# Arduino_project_board.net
KiCad netlist of a schematic drawn in EAGLE
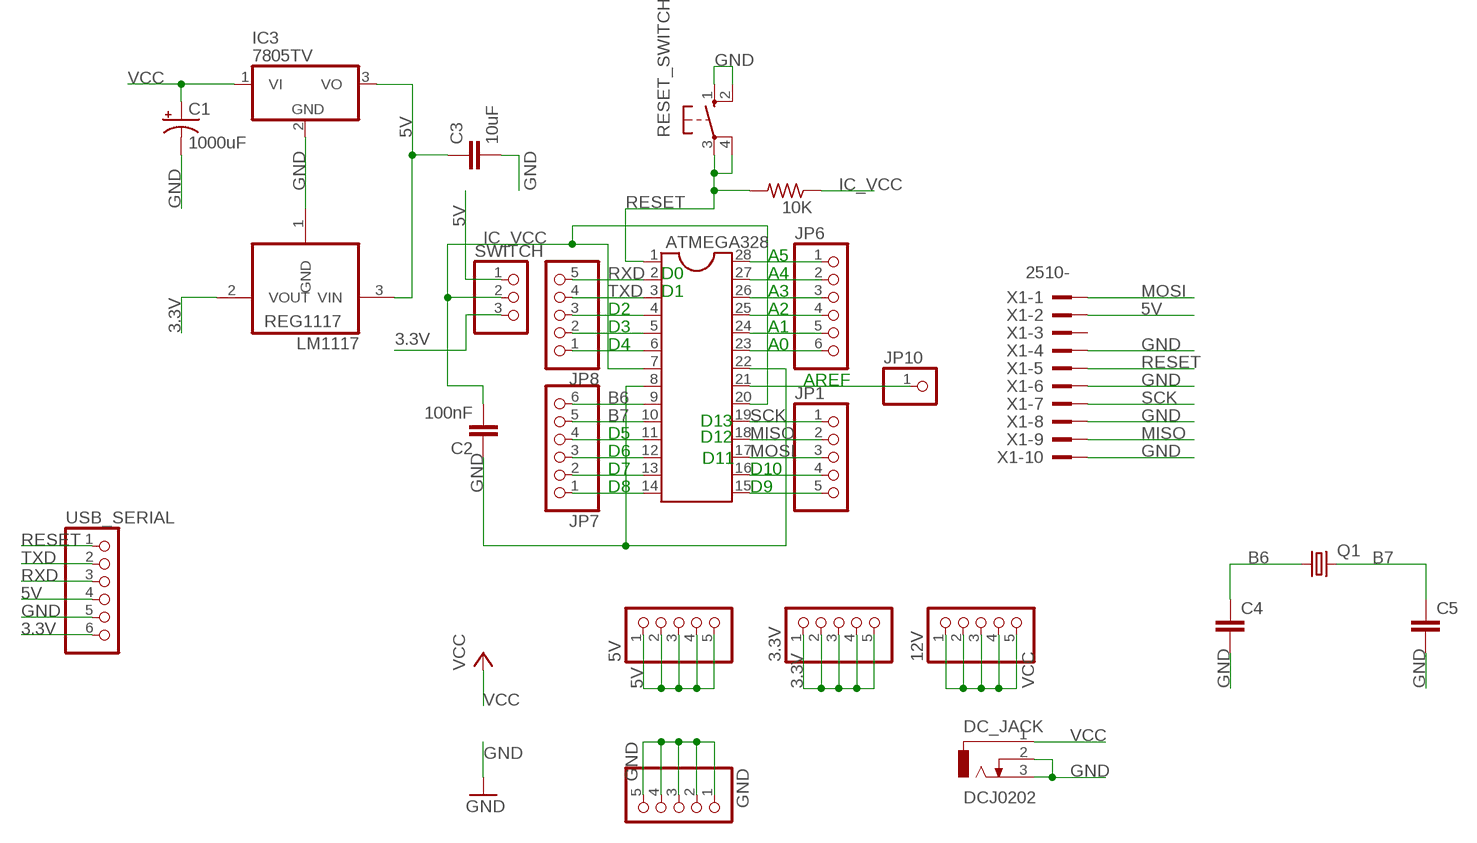
[diagram p0: schematic, sheet 1]

(export (version "E")
  (design (tool "Eeschema 10.0.6"))
  (components
    (comp (ref "3.3V")
      (value "PINHD-1X5")
      (footprint "eagle-import:1X05")
      (libsource (lib "eagle-import") (part "PINHD-1X5"))
    )
    (comp (ref "5V")
      (value "PINHD-1X5")
      (footprint "eagle-import:1X05")
      (libsource (lib "eagle-import") (part "PINHD-1X5"))
    )
    (comp (ref "10K")
      (value "R-US_R0805")
      (footprint "eagle-import:R0805")
      (libsource (lib "eagle-import") (part "R-US_R0805"))
    )
    (comp (ref "12V")
      (value "PINHD-1X5")
      (footprint "eagle-import:1X05")
      (libsource (lib "eagle-import") (part "PINHD-1X5"))
    )
    (comp (ref "ATMEGA328")
      (value "DIL28-4")
      (footprint "eagle-import:DIL28-4")
      (libsource (lib "eagle-import") (part "DIL28-4"))
    )
    (comp (ref "C1")
      (value "1000uF")
      (footprint "eagle-import:CPOL-RADIAL-1000UF-25V")
      (libsource (lib "eagle-import") (part "1000UF-25V(PTH)"))
    )
    (comp (ref "C2")
      (value "100nF")
      (footprint "eagle-import:C0805K")
      (libsource (lib "eagle-import") (part "C-EUC0805K"))
    )
    (comp (ref "C3")
      (value "10uF")
      (footprint "eagle-import:C0805K")
      (libsource (lib "eagle-import") (part "C-EUC0805K"))
    )
    (comp (ref "C4")
      (value "C-EUC0805K")
      (footprint "eagle-import:C0805K")
      (libsource (lib "eagle-import") (part "C-EUC0805K"))
    )
    (comp (ref "C5")
      (value "C-EUC0805K")
      (footprint "eagle-import:C0805K")
      (libsource (lib "eagle-import") (part "C-EUC0805K"))
    )
    (comp (ref "DC_JACK")
      (value "DCJ0202")
      (footprint "eagle-import:DCJ0202")
      (libsource (lib "eagle-import") (part "DCJ0202"))
    )
    (comp (ref "GND")
      (value "PINHD-1X5")
      (footprint "eagle-import:1X05")
      (libsource (lib "eagle-import") (part "PINHD-1X5"))
    )
    (comp (ref "IC3")
      (value "7805TV")
      (footprint "eagle-import:TO220V")
      (libsource (lib "eagle-import") (part "78TV05"))
    )
    (comp (ref "JP1")
      (value "PINHD-1X5")
      (footprint "eagle-import:1X05")
      (libsource (lib "eagle-import") (part "PINHD-1X5"))
    )
    (comp (ref "JP6")
      (value "PINHD-1X6")
      (footprint "eagle-import:1X06")
      (libsource (lib "eagle-import") (part "PINHD-1X6"))
    )
    (comp (ref "JP7")
      (value "PINHD-1X6")
      (footprint "eagle-import:1X06")
      (libsource (lib "eagle-import") (part "PINHD-1X6"))
    )
    (comp (ref "JP8")
      (value "PINHD-1X5")
      (footprint "eagle-import:1X05")
      (libsource (lib "eagle-import") (part "PINHD-1X5"))
    )
    (comp (ref "JP10")
      (value "PINHD-1X1")
      (footprint "eagle-import:1X01")
      (libsource (lib "eagle-import") (part "PINHD-1X1"))
    )
    (comp (ref "LM1117")
      (value "REG1117")
      (footprint "eagle-import:SOT223")
      (libsource (lib "eagle-import") (part "REG1117"))
    )
    (comp (ref "Q1")
      (value "CRYSTALHC49S")
      (footprint "eagle-import:HC49_S")
      (libsource (lib "eagle-import") (part "CRYSTALHC49S"))
    )
    (comp (ref "RESET_SWITCH")
      (value "10-XX")
      (footprint "eagle-import:B3F-10XX")
      (fields (field (name "MPN") "B3F-1000"))
      (libsource (lib "eagle-import") (part "10-XX"))
    )
    (comp (ref "SWITCH")
      (value "PINHD-1X3")
      (footprint "eagle-import:1X03")
      (libsource (lib "eagle-import") (part "PINHD-1X3"))
    )
    (comp (ref "USB_SERIAL")
      (value "PINHD-1X6")
      (footprint "eagle-import:1X06")
      (libsource (lib "eagle-import") (part "PINHD-1X6"))
    )
    (comp (ref "X1")
      (value "2510-")
      (footprint "eagle-import:PAK100_2500-10")
      (fields (field (name "MF") "3M") (field (name "MPN") "2510-6002UB"))
      (libsource (lib "eagle-import") (part "2510-"))
    )
  )
  (nets
    (net (code "1") (name "/3.3V") (class "Default")
      (node (ref "3.3V") (pin "1") (pinfunction "1_1") (pintype "passive"))
      (node (ref "3.3V") (pin "2") (pinfunction "2_2") (pintype "passive"))
      (node (ref "3.3V") (pin "3") (pinfunction "3_3") (pintype "passive"))
      (node (ref "3.3V") (pin "4") (pinfunction "4_4") (pintype "passive"))
      (node (ref "3.3V") (pin "5") (pinfunction "5_5") (pintype "passive"))
      (node (ref "LM1117") (pin "2") (pinfunction "VOUT_2") (pintype "output"))
      (node (ref "SWITCH") (pin "3") (pinfunction "3_3") (pintype "passive"))
      (node (ref "USB_SERIAL") (pin "6") (pinfunction "6_6") (pintype "passive"))
    )
    (net (code "2") (name "/5V") (class "Default")
      (node (ref "5V") (pin "1") (pinfunction "1_1") (pintype "passive"))
      (node (ref "5V") (pin "2") (pinfunction "2_2") (pintype "passive"))
      (node (ref "5V") (pin "3") (pinfunction "3_3") (pintype "passive"))
      (node (ref "5V") (pin "4") (pinfunction "4_4") (pintype "passive"))
      (node (ref "5V") (pin "5") (pinfunction "5_5") (pintype "passive"))
      (node (ref "C3") (pin "1") (pinfunction "1_1") (pintype "passive"))
      (node (ref "IC3") (pin "3") (pinfunction "VO_3") (pintype "passive"))
      (node (ref "LM1117") (pin "3") (pinfunction "VIN_3") (pintype "input"))
      (node (ref "SWITCH") (pin "1") (pinfunction "1_1") (pintype "passive"))
      (node (ref "USB_SERIAL") (pin "4") (pinfunction "4_4") (pintype "passive"))
      (node (ref "X1") (pin "2") (pinfunction "KL_2") (pintype "passive"))
    )
    (net (code "3") (name "/B6") (class "Default")
      (node (ref "ATMEGA328") (pin "9") (pinfunction "9_9") (pintype "passive"))
      (node (ref "C4") (pin "1") (pinfunction "1_1") (pintype "passive"))
      (node (ref "JP7") (pin "6") (pinfunction "6_6") (pintype "passive"))
      (node (ref "Q1") (pin "1") (pinfunction "1_1") (pintype "passive"))
    )
    (net (code "4") (name "/B7") (class "Default")
      (node (ref "ATMEGA328") (pin "10") (pinfunction "10_10") (pintype "passive"))
      (node (ref "C5") (pin "1") (pinfunction "1_1") (pintype "passive"))
      (node (ref "JP7") (pin "5") (pinfunction "5_5") (pintype "passive"))
      (node (ref "Q1") (pin "2") (pinfunction "2_2") (pintype "passive"))
    )
    (net (code "5") (name "/IC_VCC") (class "Default")
      (node (ref "10K") (pin "1") (pinfunction "1_1") (pintype "passive"))
      (node (ref "ATMEGA328") (pin "20") (pinfunction "20_20") (pintype "passive"))
      (node (ref "ATMEGA328") (pin "7") (pinfunction "7_7") (pintype "passive"))
      (node (ref "C2") (pin "2") (pinfunction "2_2") (pintype "passive"))
      (node (ref "SWITCH") (pin "2") (pinfunction "2_2") (pintype "passive"))
    )
    (net (code "6") (name "/MISO") (class "Default")
      (node (ref "ATMEGA328") (pin "18") (pinfunction "18_18") (pintype "passive"))
      (node (ref "JP1") (pin "2") (pinfunction "2_2") (pintype "passive"))
      (node (ref "X1") (pin "9") (pinfunction "KL_9") (pintype "passive"))
    )
    (net (code "7") (name "/MOSI") (class "Default")
      (node (ref "ATMEGA328") (pin "17") (pinfunction "17_17") (pintype "passive"))
      (node (ref "JP1") (pin "3") (pinfunction "3_3") (pintype "passive"))
      (node (ref "X1") (pin "1") (pinfunction "KL_1") (pintype "passive"))
    )
    (net (code "8") (name "/RESET") (class "Default")
      (node (ref "10K") (pin "2") (pinfunction "2_2") (pintype "passive"))
      (node (ref "ATMEGA328") (pin "1") (pinfunction "1_1") (pintype "passive"))
      (node (ref "RESET_SWITCH") (pin "3") (pinfunction "P_3") (pintype "passive"))
      (node (ref "RESET_SWITCH") (pin "4") (pinfunction "P1_4") (pintype "passive"))
      (node (ref "USB_SERIAL") (pin "1") (pinfunction "1_1") (pintype "passive"))
      (node (ref "X1") (pin "5") (pinfunction "KL_5") (pintype "passive"))
    )
    (net (code "9") (name "/RXD") (class "Default")
      (node (ref "ATMEGA328") (pin "2") (pinfunction "2_2") (pintype "passive"))
      (node (ref "JP8") (pin "5") (pinfunction "5_5") (pintype "passive"))
      (node (ref "USB_SERIAL") (pin "3") (pinfunction "3_3") (pintype "passive"))
    )
    (net (code "10") (name "/SCK") (class "Default")
      (node (ref "ATMEGA328") (pin "19") (pinfunction "19_19") (pintype "passive"))
      (node (ref "JP1") (pin "1") (pinfunction "1_1") (pintype "passive"))
      (node (ref "X1") (pin "7") (pinfunction "KL_7") (pintype "passive"))
    )
    (net (code "11") (name "/TXD") (class "Default")
      (node (ref "ATMEGA328") (pin "3") (pinfunction "3_3") (pintype "passive"))
      (node (ref "JP8") (pin "4") (pinfunction "4_4") (pintype "passive"))
      (node (ref "USB_SERIAL") (pin "2") (pinfunction "2_2") (pintype "passive"))
    )
    (net (code "12") (name "GND") (class "Default")
      (node (ref "ATMEGA328") (pin "22") (pinfunction "22_22") (pintype "passive"))
      (node (ref "ATMEGA328") (pin "8") (pinfunction "8_8") (pintype "passive"))
      (node (ref "C1") (pin "-") (pinfunction "-_-") (pintype "passive"))
      (node (ref "C2") (pin "1") (pinfunction "1_1") (pintype "passive"))
      (node (ref "C3") (pin "2") (pinfunction "2_2") (pintype "passive"))
      (node (ref "C4") (pin "2") (pinfunction "2_2") (pintype "passive"))
      (node (ref "C5") (pin "2") (pinfunction "2_2") (pintype "passive"))
      (node (ref "DC_JACK") (pin "2") (pinfunction "2_2") (pintype "passive"))
      (node (ref "DC_JACK") (pin "3") (pinfunction "3_3") (pintype "passive"))
      (node (ref "GND") (pin "1") (pinfunction "1_1") (pintype "passive"))
      (node (ref "GND") (pin "2") (pinfunction "2_2") (pintype "passive"))
      (node (ref "GND") (pin "3") (pinfunction "3_3") (pintype "passive"))
      (node (ref "GND") (pin "4") (pinfunction "4_4") (pintype "passive"))
      (node (ref "GND") (pin "5") (pinfunction "5_5") (pintype "passive"))
      (node (ref "IC3") (pin "2") (pinfunction "GND_2") (pintype "passive"))
      (node (ref "LM1117") (pin "1") (pinfunction "GND_1") (pintype "power_in"))
      (node (ref "RESET_SWITCH") (pin "1") (pinfunction "S_1") (pintype "passive"))
      (node (ref "RESET_SWITCH") (pin "2") (pinfunction "S1_2") (pintype "passive"))
      (node (ref "USB_SERIAL") (pin "5") (pinfunction "5_5") (pintype "passive"))
      (node (ref "X1") (pin "10") (pinfunction "KL_10") (pintype "passive"))
      (node (ref "X1") (pin "4") (pinfunction "KL_4") (pintype "passive"))
      (node (ref "X1") (pin "6") (pinfunction "KL_6") (pintype "passive"))
      (node (ref "X1") (pin "8") (pinfunction "KL_8") (pintype "passive"))
    )
    (net (code "13") (name "Net-(ATMEGA328-Pad4)") (class "Default")
      (node (ref "ATMEGA328") (pin "4") (pinfunction "4_4") (pintype "passive"))
      (node (ref "JP8") (pin "3") (pinfunction "3_3") (pintype "passive"))
    )
    (net (code "14") (name "Net-(ATMEGA328-Pad5)") (class "Default")
      (node (ref "ATMEGA328") (pin "5") (pinfunction "5_5") (pintype "passive"))
      (node (ref "JP8") (pin "2") (pinfunction "2_2") (pintype "passive"))
    )
    (net (code "15") (name "Net-(ATMEGA328-Pad6)") (class "Default")
      (node (ref "ATMEGA328") (pin "6") (pinfunction "6_6") (pintype "passive"))
      (node (ref "JP8") (pin "1") (pinfunction "1_1") (pintype "passive"))
    )
    (net (code "16") (name "Net-(ATMEGA328-Pad11)") (class "Default")
      (node (ref "ATMEGA328") (pin "11") (pinfunction "11_11") (pintype "passive"))
      (node (ref "JP7") (pin "4") (pinfunction "4_4") (pintype "passive"))
    )
    (net (code "17") (name "Net-(ATMEGA328-Pad12)") (class "Default")
      (node (ref "ATMEGA328") (pin "12") (pinfunction "12_12") (pintype "passive"))
      (node (ref "JP7") (pin "3") (pinfunction "3_3") (pintype "passive"))
    )
    (net (code "18") (name "Net-(ATMEGA328-Pad13)") (class "Default")
      (node (ref "ATMEGA328") (pin "13") (pinfunction "13_13") (pintype "passive"))
      (node (ref "JP7") (pin "2") (pinfunction "2_2") (pintype "passive"))
    )
    (net (code "19") (name "Net-(ATMEGA328-Pad14)") (class "Default")
      (node (ref "ATMEGA328") (pin "14") (pinfunction "14_14") (pintype "passive"))
      (node (ref "JP7") (pin "1") (pinfunction "1_1") (pintype "passive"))
    )
    (net (code "20") (name "Net-(ATMEGA328-Pad15)") (class "Default")
      (node (ref "ATMEGA328") (pin "15") (pinfunction "15_15") (pintype "passive"))
      (node (ref "JP1") (pin "5") (pinfunction "5_5") (pintype "passive"))
    )
    (net (code "21") (name "Net-(ATMEGA328-Pad16)") (class "Default")
      (node (ref "ATMEGA328") (pin "16") (pinfunction "16_16") (pintype "passive"))
      (node (ref "JP1") (pin "4") (pinfunction "4_4") (pintype "passive"))
    )
    (net (code "22") (name "Net-(ATMEGA328-Pad21)") (class "Default")
      (node (ref "ATMEGA328") (pin "21") (pinfunction "21_21") (pintype "passive"))
      (node (ref "JP10") (pin "1") (pinfunction "1_1") (pintype "passive"))
    )
    (net (code "23") (name "Net-(ATMEGA328-Pad23)") (class "Default")
      (node (ref "ATMEGA328") (pin "23") (pinfunction "23_23") (pintype "passive"))
      (node (ref "JP6") (pin "6") (pinfunction "6_6") (pintype "passive"))
    )
    (net (code "24") (name "Net-(ATMEGA328-Pad24)") (class "Default")
      (node (ref "ATMEGA328") (pin "24") (pinfunction "24_24") (pintype "passive"))
      (node (ref "JP6") (pin "5") (pinfunction "5_5") (pintype "passive"))
    )
    (net (code "25") (name "Net-(ATMEGA328-Pad25)") (class "Default")
      (node (ref "ATMEGA328") (pin "25") (pinfunction "25_25") (pintype "passive"))
      (node (ref "JP6") (pin "4") (pinfunction "4_4") (pintype "passive"))
    )
    (net (code "26") (name "Net-(ATMEGA328-Pad26)") (class "Default")
      (node (ref "ATMEGA328") (pin "26") (pinfunction "26_26") (pintype "passive"))
      (node (ref "JP6") (pin "3") (pinfunction "3_3") (pintype "passive"))
    )
    (net (code "27") (name "Net-(ATMEGA328-Pad27)") (class "Default")
      (node (ref "ATMEGA328") (pin "27") (pinfunction "27_27") (pintype "passive"))
      (node (ref "JP6") (pin "2") (pinfunction "2_2") (pintype "passive"))
    )
    (net (code "28") (name "Net-(ATMEGA328-Pad28)") (class "Default")
      (node (ref "ATMEGA328") (pin "28") (pinfunction "28_28") (pintype "passive"))
      (node (ref "JP6") (pin "1") (pinfunction "1_1") (pintype "passive"))
    )
    (net (code "29") (name "VCC") (class "Default")
      (node (ref "12V") (pin "1") (pinfunction "1_1") (pintype "passive"))
      (node (ref "12V") (pin "2") (pinfunction "2_2") (pintype "passive"))
      (node (ref "12V") (pin "3") (pinfunction "3_3") (pintype "passive"))
      (node (ref "12V") (pin "4") (pinfunction "4_4") (pintype "passive"))
      (node (ref "12V") (pin "5") (pinfunction "5_5") (pintype "passive"))
      (node (ref "C1") (pin "+") (pinfunction "+_+") (pintype "passive"))
      (node (ref "DC_JACK") (pin "1") (pinfunction "1_1") (pintype "passive"))
      (node (ref "IC3") (pin "1") (pinfunction "VI_1") (pintype "input"))
    )
    (net (code "30") (name "unconnected-(X1D-KL-Pad3)") (class "Default")
      (node (ref "X1") (pin "3") (pinfunction "KL_3") (pintype "passive"))
    )
  )
)
